# noise-generator.net
KiCad netlist of a schematic drawn in EAGLE
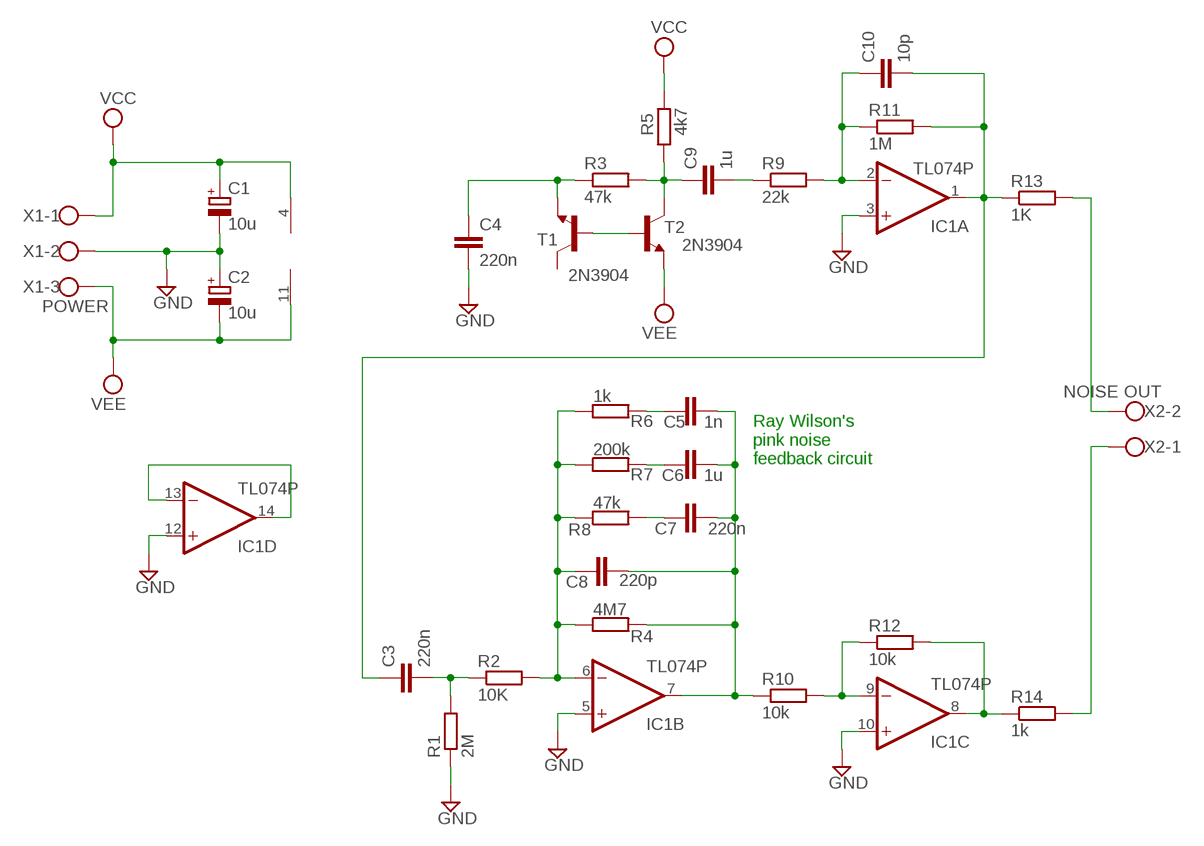
[diagram p0: schematic, sheet 1]

(export (version "E")
  (design (tool "Eeschema 10.0.6"))
  (components
    (comp (ref "C1")
      (value "10u")
      (footprint "eagle-import:E1,8-4")
      (libsource (lib "eagle-import") (part "CPOL-EUE1.8-4"))
    )
    (comp (ref "C2")
      (value "10u")
      (footprint "eagle-import:E1,8-4")
      (libsource (lib "eagle-import") (part "CPOL-EUE1.8-4"))
    )
    (comp (ref "C3")
      (value "220n")
      (footprint "eagle-import:C050-024X044")
      (libsource (lib "eagle-import") (part "C-EU050-024X044"))
    )
    (comp (ref "C4")
      (value "220n")
      (footprint "eagle-import:C050-024X044")
      (libsource (lib "eagle-import") (part "C-EU050-024X044"))
    )
    (comp (ref "C5")
      (value "1n")
      (footprint "eagle-import:C050-024X044")
      (libsource (lib "eagle-import") (part "C-EU050-024X044"))
    )
    (comp (ref "C6")
      (value "1u")
      (footprint "eagle-import:C050-024X044")
      (libsource (lib "eagle-import") (part "C-EU050-024X044"))
    )
    (comp (ref "C7")
      (value "220n")
      (footprint "eagle-import:C050-024X044")
      (libsource (lib "eagle-import") (part "C-EU050-024X044"))
    )
    (comp (ref "C8")
      (value "220p")
      (footprint "eagle-import:C050-024X044")
      (libsource (lib "eagle-import") (part "C-EU050-024X044"))
    )
    (comp (ref "C9")
      (value "1u")
      (footprint "eagle-import:C050-024X044")
      (libsource (lib "eagle-import") (part "C-EU050-024X044"))
    )
    (comp (ref "C10")
      (value "10p")
      (footprint "eagle-import:C025-024X044")
      (libsource (lib "eagle-import") (part "C-EU025-024X044"))
    )
    (comp (ref "IC1")
      (value "TL074P")
      (footprint "eagle-import:DIL14")
      (libsource (lib "eagle-import") (part "TL074P"))
    )
    (comp (ref "R1")
      (value "2M")
      (footprint "eagle-import:0204_7")
      (libsource (lib "eagle-import") (part "R-EU_0204/7"))
    )
    (comp (ref "R2")
      (value "10K")
      (footprint "eagle-import:0204_7")
      (libsource (lib "eagle-import") (part "R-EU_0204/7"))
    )
    (comp (ref "R3")
      (value "47k")
      (footprint "eagle-import:0204_7")
      (libsource (lib "eagle-import") (part "R-EU_0204/7"))
    )
    (comp (ref "R4")
      (value "4M7")
      (footprint "eagle-import:0204_7")
      (libsource (lib "eagle-import") (part "R-EU_0204/7"))
    )
    (comp (ref "R5")
      (value "4k7")
      (footprint "eagle-import:0204_7")
      (libsource (lib "eagle-import") (part "R-EU_0204/7"))
    )
    (comp (ref "R6")
      (value "1k")
      (footprint "eagle-import:0204_7")
      (libsource (lib "eagle-import") (part "R-EU_0204/7"))
    )
    (comp (ref "R7")
      (value "200k")
      (footprint "eagle-import:0204_7")
      (libsource (lib "eagle-import") (part "R-EU_0204/7"))
    )
    (comp (ref "R8")
      (value "47k")
      (footprint "eagle-import:0204_7")
      (libsource (lib "eagle-import") (part "R-EU_0204/7"))
    )
    (comp (ref "R9")
      (value "22k")
      (footprint "eagle-import:0204_7")
      (libsource (lib "eagle-import") (part "R-EU_0204/7"))
    )
    (comp (ref "R10")
      (value "10k")
      (footprint "eagle-import:0204_7")
      (libsource (lib "eagle-import") (part "R-EU_0204/7"))
    )
    (comp (ref "R11")
      (value "1M")
      (footprint "eagle-import:0204_7")
      (libsource (lib "eagle-import") (part "R-EU_0204/7"))
    )
    (comp (ref "R12")
      (value "10k")
      (footprint "eagle-import:0204_7")
      (libsource (lib "eagle-import") (part "R-EU_0204/7"))
    )
    (comp (ref "R13")
      (value "1K")
      (footprint "eagle-import:0204_7")
      (libsource (lib "eagle-import") (part "R-EU_0204/7"))
    )
    (comp (ref "R14")
      (value "1k")
      (footprint "eagle-import:0204_7")
      (libsource (lib "eagle-import") (part "R-EU_0204/7"))
    )
    (comp (ref "T1")
      (value "2N3904")
      (footprint "eagle-import:TO92")
      (libsource (lib "eagle-import") (part "2N3904"))
    )
    (comp (ref "T2")
      (value "2N3904")
      (footprint "eagle-import:TO92")
      (libsource (lib "eagle-import") (part "2N3904"))
    )
    (comp (ref "X1")
      (value "POWER")
      (footprint "eagle-import:W237-103")
      (fields (field (name "MPN") "237-103"))
      (libsource (lib "eagle-import") (part "W237-103"))
    )
    (comp (ref "X2")
      (value "NOISE OUT")
      (footprint "eagle-import:W237-102")
      (fields (field (name "MPN") "237-102"))
      (libsource (lib "eagle-import") (part "W237-102"))
    )
  )
  (nets
    (net (code "1") (name "GND") (class "Default")
      (node (ref "C1") (pin "-") (pinfunction "-_-") (pintype "passive"))
      (node (ref "C2") (pin "+") (pinfunction "+_+") (pintype "passive"))
      (node (ref "C4") (pin "2") (pinfunction "2_2") (pintype "passive"))
      (node (ref "IC1") (pin "10") (pinfunction "+IN_10") (pintype "input"))
      (node (ref "IC1") (pin "12") (pinfunction "+IN_12") (pintype "input"))
      (node (ref "IC1") (pin "3") (pinfunction "+IN_3") (pintype "input"))
      (node (ref "IC1") (pin "5") (pinfunction "+IN_5") (pintype "input"))
      (node (ref "R1") (pin "1") (pinfunction "1_1") (pintype "passive"))
      (node (ref "X1") (pin "2") (pinfunction "KL_2") (pintype "passive"))
    )
    (net (code "2") (name "Net-(C3-Pad2)") (class "Default")
      (node (ref "C3") (pin "2") (pinfunction "2_2") (pintype "passive"))
      (node (ref "R1") (pin "2") (pinfunction "2_2") (pintype "passive"))
      (node (ref "R2") (pin "1") (pinfunction "1_1") (pintype "passive"))
    )
    (net (code "3") (name "Net-(C5-Pad1)") (class "Default")
      (node (ref "C5") (pin "1") (pinfunction "1_1") (pintype "passive"))
      (node (ref "R6") (pin "2") (pinfunction "2_2") (pintype "passive"))
    )
    (net (code "4") (name "Net-(C6-Pad1)") (class "Default")
      (node (ref "C6") (pin "1") (pinfunction "1_1") (pintype "passive"))
      (node (ref "R7") (pin "2") (pinfunction "2_2") (pintype "passive"))
    )
    (net (code "5") (name "Net-(C7-Pad1)") (class "Default")
      (node (ref "C7") (pin "1") (pinfunction "1_1") (pintype "passive"))
      (node (ref "R8") (pin "2") (pinfunction "2_2") (pintype "passive"))
    )
    (net (code "6") (name "Net-(C9-Pad2)") (class "Default")
      (node (ref "C9") (pin "2") (pinfunction "2_2") (pintype "passive"))
      (node (ref "R9") (pin "1") (pinfunction "1_1") (pintype "passive"))
    )
    (net (code "7") (name "Net-(IC1A--IN)") (class "Default")
      (node (ref "C10") (pin "1") (pinfunction "1_1") (pintype "passive"))
      (node (ref "IC1") (pin "2") (pinfunction "-IN_2") (pintype "input"))
      (node (ref "R11") (pin "1") (pinfunction "1_1") (pintype "passive"))
      (node (ref "R9") (pin "2") (pinfunction "2_2") (pintype "passive"))
    )
    (net (code "8") (name "Net-(IC1A-OUT)") (class "Default")
      (node (ref "C10") (pin "2") (pinfunction "2_2") (pintype "passive"))
      (node (ref "C3") (pin "1") (pinfunction "1_1") (pintype "passive"))
      (node (ref "IC1") (pin "1") (pinfunction "OUT_1") (pintype "output"))
      (node (ref "R11") (pin "2") (pinfunction "2_2") (pintype "passive"))
      (node (ref "R13") (pin "1") (pinfunction "1_1") (pintype "passive"))
    )
    (net (code "9") (name "Net-(IC1B--IN)") (class "Default")
      (node (ref "C8") (pin "1") (pinfunction "1_1") (pintype "passive"))
      (node (ref "IC1") (pin "6") (pinfunction "-IN_6") (pintype "input"))
      (node (ref "R2") (pin "2") (pinfunction "2_2") (pintype "passive"))
      (node (ref "R4") (pin "1") (pinfunction "1_1") (pintype "passive"))
      (node (ref "R6") (pin "1") (pinfunction "1_1") (pintype "passive"))
      (node (ref "R7") (pin "1") (pinfunction "1_1") (pintype "passive"))
      (node (ref "R8") (pin "1") (pinfunction "1_1") (pintype "passive"))
    )
    (net (code "10") (name "Net-(IC1B-OUT)") (class "Default")
      (node (ref "C5") (pin "2") (pinfunction "2_2") (pintype "passive"))
      (node (ref "C6") (pin "2") (pinfunction "2_2") (pintype "passive"))
      (node (ref "C7") (pin "2") (pinfunction "2_2") (pintype "passive"))
      (node (ref "C8") (pin "2") (pinfunction "2_2") (pintype "passive"))
      (node (ref "IC1") (pin "7") (pinfunction "OUT_7") (pintype "output"))
      (node (ref "R10") (pin "1") (pinfunction "1_1") (pintype "passive"))
      (node (ref "R4") (pin "2") (pinfunction "2_2") (pintype "passive"))
    )
    (net (code "11") (name "Net-(IC1C--IN)") (class "Default")
      (node (ref "IC1") (pin "9") (pinfunction "-IN_9") (pintype "input"))
      (node (ref "R10") (pin "2") (pinfunction "2_2") (pintype "passive"))
      (node (ref "R12") (pin "1") (pinfunction "1_1") (pintype "passive"))
    )
    (net (code "12") (name "Net-(IC1C-OUT)") (class "Default")
      (node (ref "IC1") (pin "8") (pinfunction "OUT_8") (pintype "output"))
      (node (ref "R12") (pin "2") (pinfunction "2_2") (pintype "passive"))
      (node (ref "R14") (pin "1") (pinfunction "1_1") (pintype "passive"))
    )
    (net (code "13") (name "Net-(IC1D--IN)") (class "Default")
      (node (ref "IC1") (pin "13") (pinfunction "-IN_13") (pintype "input"))
      (node (ref "IC1") (pin "14") (pinfunction "OUT_14") (pintype "output"))
    )
    (net (code "14") (name "Net-(T1-B)") (class "Default")
      (node (ref "T1") (pin "2") (pinfunction "B_2") (pintype "passive"))
      (node (ref "T2") (pin "2") (pinfunction "B_2") (pintype "passive"))
    )
    (net (code "15") (name "Net-(T1-E)") (class "Default")
      (node (ref "C4") (pin "1") (pinfunction "1_1") (pintype "passive"))
      (node (ref "R3") (pin "1") (pinfunction "1_1") (pintype "passive"))
      (node (ref "T1") (pin "3") (pinfunction "E_3") (pintype "passive"))
    )
    (net (code "16") (name "Net-(T2-C)") (class "Default")
      (node (ref "C9") (pin "1") (pinfunction "1_1") (pintype "passive"))
      (node (ref "R3") (pin "2") (pinfunction "2_2") (pintype "passive"))
      (node (ref "R5") (pin "1") (pinfunction "1_1") (pintype "passive"))
      (node (ref "T2") (pin "1") (pinfunction "C_1") (pintype "passive"))
    )
    (net (code "17") (name "Net-(X2A-KL)") (class "Default")
      (node (ref "R14") (pin "2") (pinfunction "2_2") (pintype "passive"))
      (node (ref "X2") (pin "1") (pinfunction "KL_1") (pintype "passive"))
    )
    (net (code "18") (name "Net-(X2B-KL)") (class "Default")
      (node (ref "R13") (pin "2") (pinfunction "2_2") (pintype "passive"))
      (node (ref "X2") (pin "2") (pinfunction "KL_2") (pintype "passive"))
    )
    (net (code "19") (name "VCC") (class "Default")
      (node (ref "C1") (pin "+") (pinfunction "+_+") (pintype "passive"))
      (node (ref "IC1") (pin "4") (pinfunction "V+_4") (pintype "power_in"))
      (node (ref "R5") (pin "2") (pinfunction "2_2") (pintype "passive"))
      (node (ref "X1") (pin "1") (pinfunction "KL_1") (pintype "passive"))
    )
    (net (code "20") (name "VEE") (class "Default")
      (node (ref "C2") (pin "-") (pinfunction "-_-") (pintype "passive"))
      (node (ref "IC1") (pin "11") (pinfunction "V-_11") (pintype "power_in"))
      (node (ref "T2") (pin "3") (pinfunction "E_3") (pintype "passive"))
      (node (ref "X1") (pin "3") (pinfunction "KL_3") (pintype "passive"))
    )
    (net (code "21") (name "unconnected-(T1-C-Pad1)") (class "Default")
      (node (ref "T1") (pin "1") (pinfunction "C_1") (pintype "passive"))
    )
  )
)
